# Adafruit_Feather_Zero_BLE_rev_B.net
KiCad netlist of a schematic drawn in EAGLE
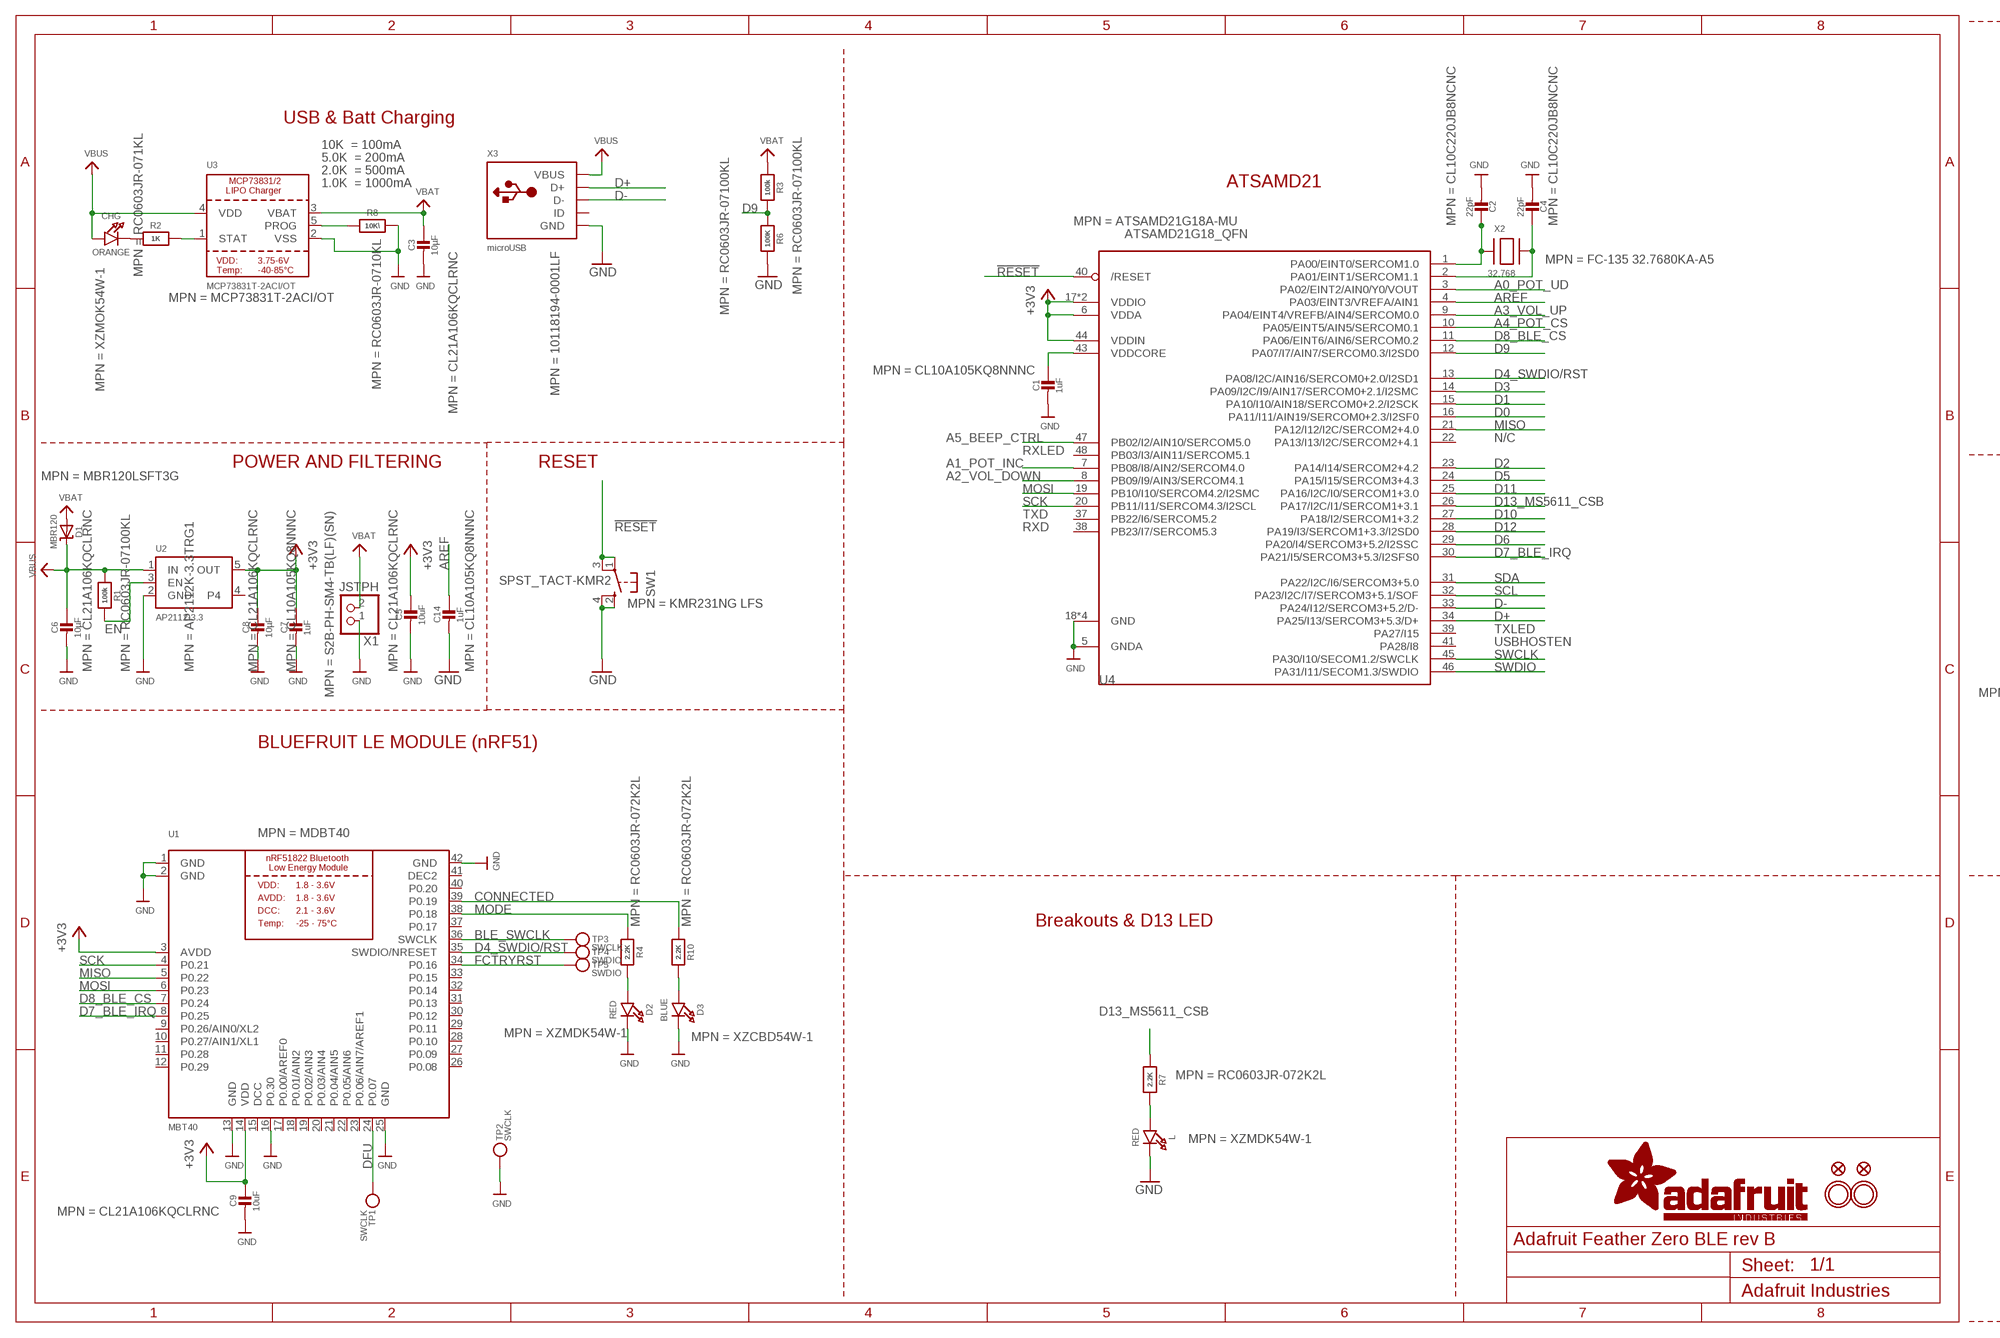
[diagram p0: schematic, sheet 1, part 1 of 2]
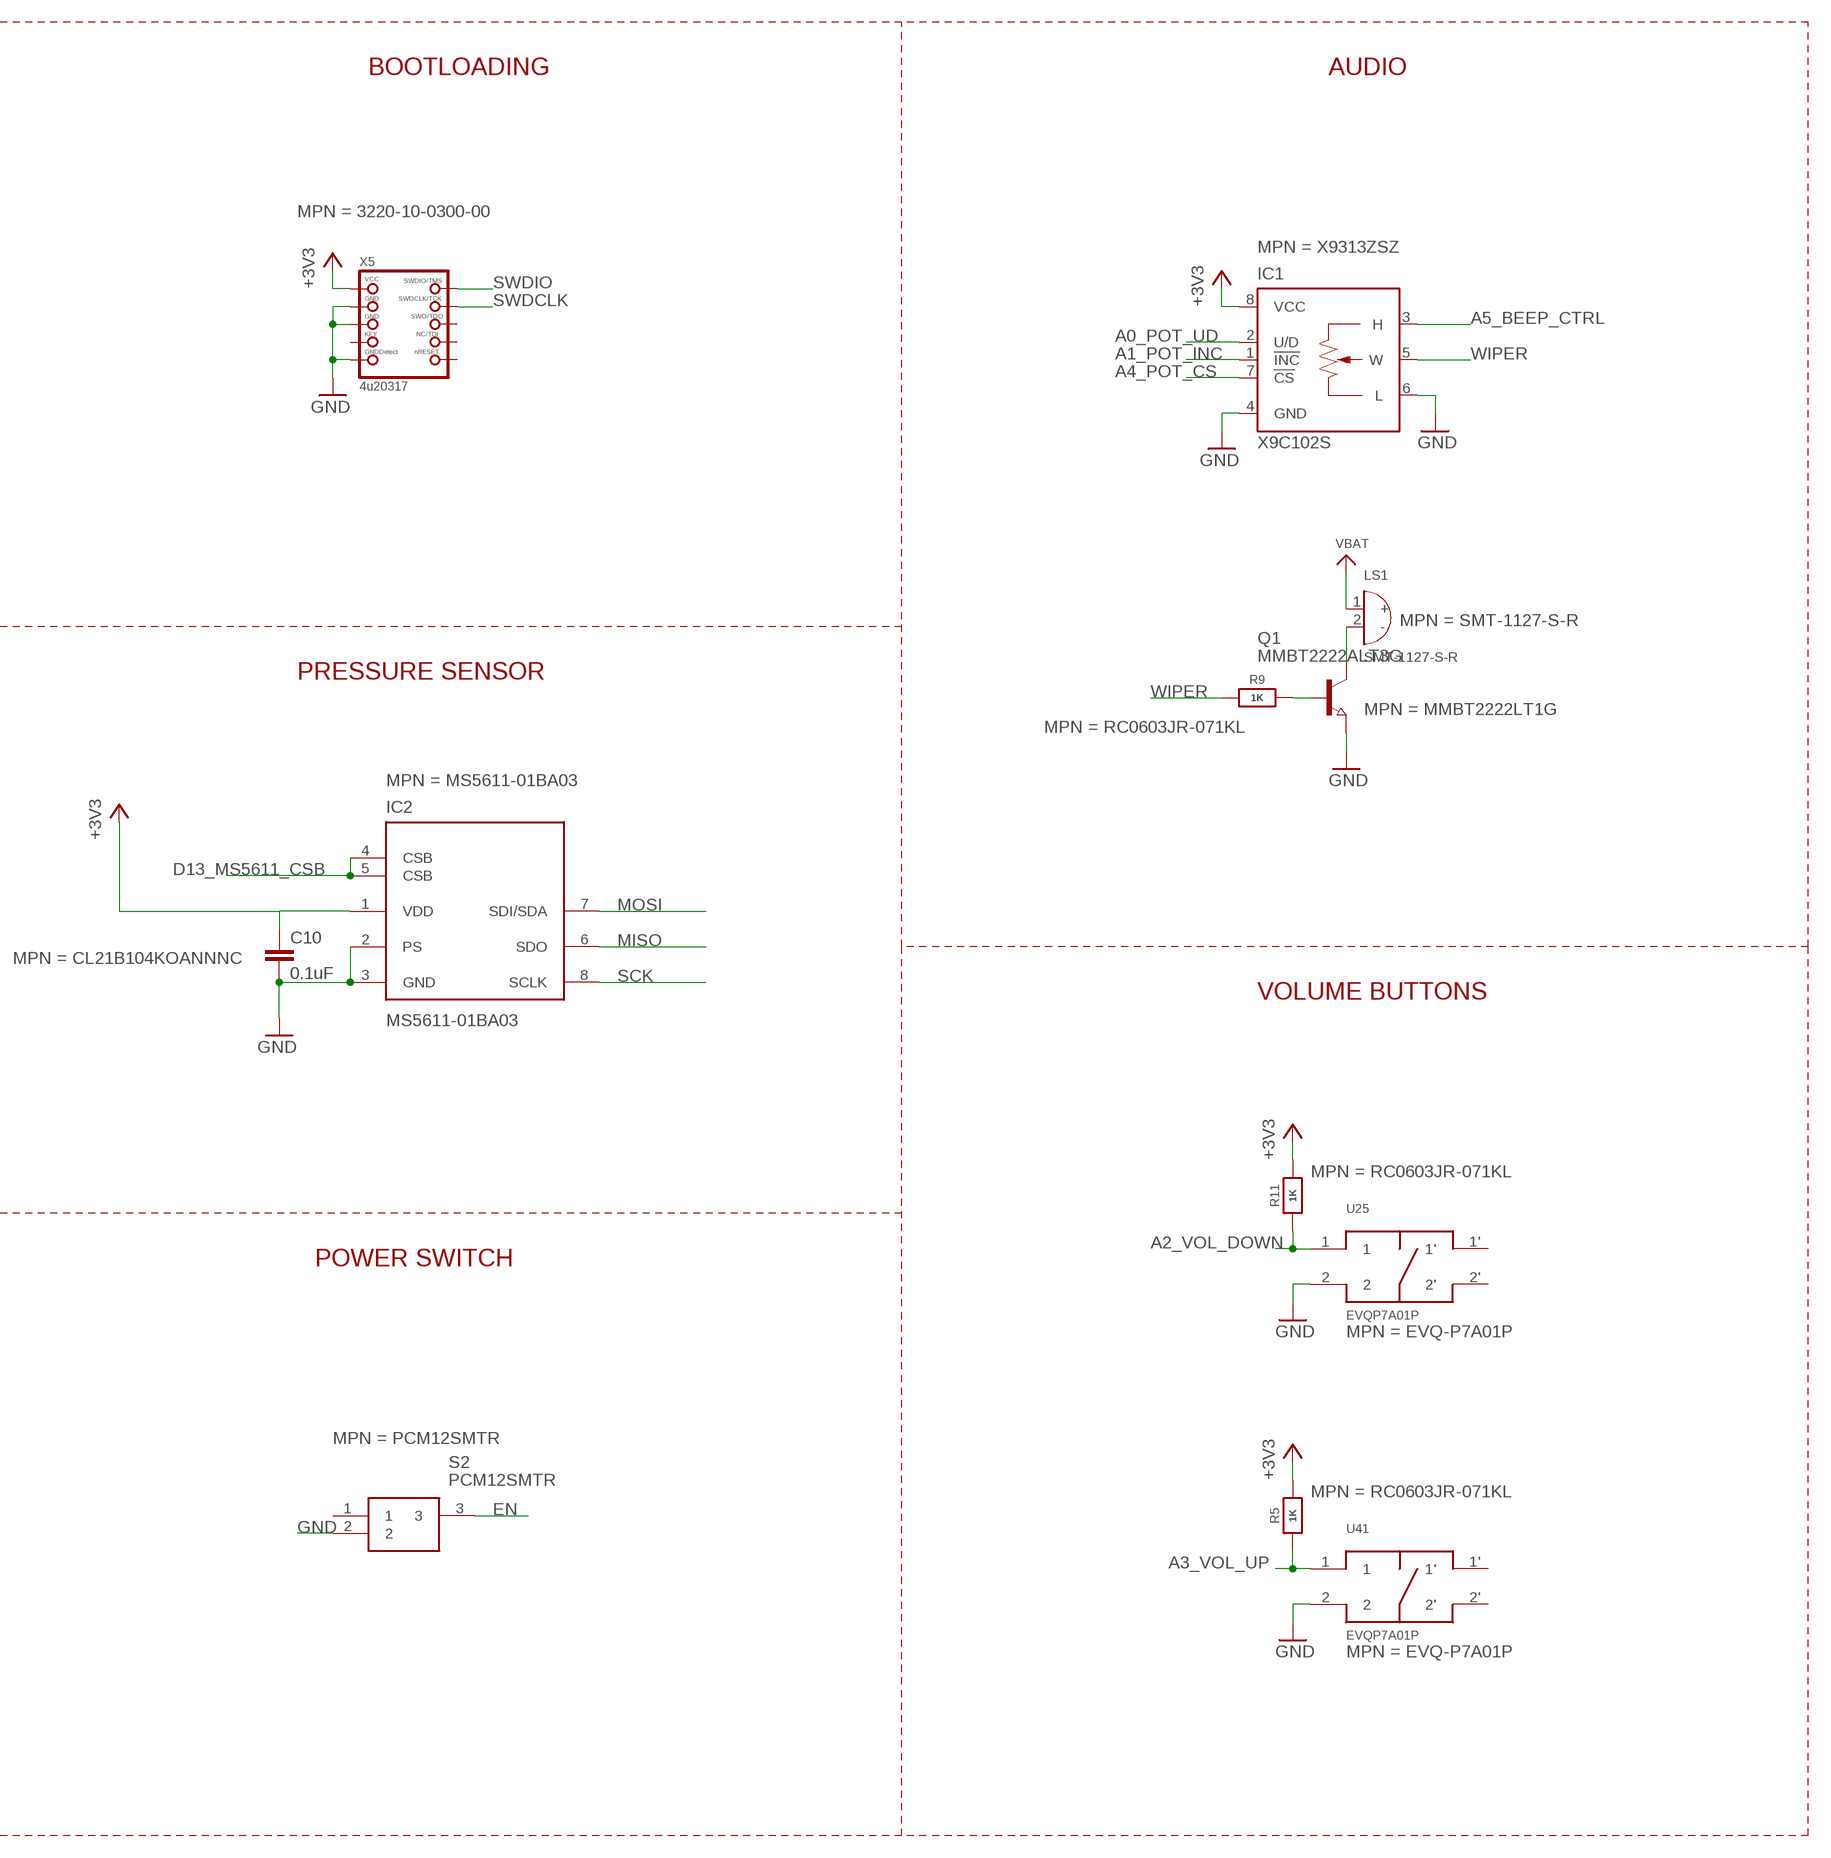
[diagram p1: schematic, sheet 1, part 2 of 2]

(export (version "E")
  (design (tool "Eeschema 10.0.6"))
  (components
    (comp (ref "C1")
      (value "1uF")
      (footprint "eagle-import:0603-NO")
      (fields (field (name "MPN") "CL10A105KQ8NNNC"))
      (libsource (lib "eagle-import") (part "CAP_CERAMIC0603_NO"))
    )
    (comp (ref "C2")
      (value "22pF")
      (footprint "eagle-import:0603-NO")
      (fields (field (name "MPN") "CL10C220JB8NCNC"))
      (libsource (lib "eagle-import") (part "CAP_CERAMIC0603_NO"))
    )
    (comp (ref "C3")
      (value "10µF")
      (footprint "eagle-import:0805-NO")
      (fields (field (name "MPN") "CL21A106KQCLRNC"))
      (libsource (lib "eagle-import") (part "CAP_CERAMIC0805-NOOUTLINE"))
    )
    (comp (ref "C4")
      (value "22pF")
      (footprint "eagle-import:0603-NO")
      (fields (field (name "MPN") "CL10C220JB8NCNC"))
      (libsource (lib "eagle-import") (part "CAP_CERAMIC0603_NO"))
    )
    (comp (ref "C5")
      (value "10uF")
      (footprint "eagle-import:0805-NO")
      (fields (field (name "MPN") "CL21A106KQCLRNC"))
      (libsource (lib "eagle-import") (part "CAP_CERAMIC0805-NOOUTLINE"))
    )
    (comp (ref "C6")
      (value "10µF")
      (footprint "eagle-import:0805-NO")
      (fields (field (name "MPN") "CL21A106KQCLRNC"))
      (libsource (lib "eagle-import") (part "CAP_CERAMIC0805-NOOUTLINE"))
    )
    (comp (ref "C7")
      (value "1uF")
      (footprint "eagle-import:0603-NO")
      (fields (field (name "MPN") "CL10A105KQ8NNNC"))
      (libsource (lib "eagle-import") (part "CAP_CERAMIC0603_NO"))
    )
    (comp (ref "C8")
      (value "10µF")
      (footprint "eagle-import:0805-NO")
      (fields (field (name "MPN") "CL21A106KQCLRNC"))
      (libsource (lib "eagle-import") (part "CAP_CERAMIC0805-NOOUTLINE"))
    )
    (comp (ref "C9")
      (value "10uF")
      (footprint "eagle-import:0805-NO")
      (fields (field (name "MPN") "CL21A106KQCLRNC"))
      (libsource (lib "eagle-import") (part "CAP_CERAMIC0805-NOOUTLINE"))
    )
    (comp (ref "C10")
      (value "0.1uF")
      (footprint "eagle-import:C0805K")
      (fields (field (name "MPN") "CL21B104KOANNNC"))
      (libsource (lib "eagle-import") (part "C-EUC0805K"))
    )
    (comp (ref "C14")
      (value "1uF")
      (footprint "eagle-import:0603-NO")
      (fields (field (name "MPN") "CL10A105KQ8NNNC"))
      (libsource (lib "eagle-import") (part "CAP_CERAMIC0603_NO"))
    )
    (comp (ref "CHG")
      (value "ORANGE")
      (footprint "eagle-import:CHIPLED_0805_NOOUTLINE")
      (fields (field (name "MPN") "XZMOK54W-1"))
      (libsource (lib "eagle-import") (part "LED0805_NOOUTLINE"))
    )
    (comp (ref "D1")
      (value "MBR120")
      (footprint "eagle-import:SOD-123")
      (fields (field (name "MPN") "MBR120LSFT3G"))
      (libsource (lib "eagle-import") (part "DIODE-SCHOTTKYSOD-123"))
    )
    (comp (ref "D2")
      (value "RED")
      (footprint "eagle-import:CHIPLED_0805_NOOUTLINE")
      (fields (field (name "MPN") "XZMDK54W-1"))
      (libsource (lib "eagle-import") (part "LED0805_NOOUTLINE"))
    )
    (comp (ref "D3")
      (value "BLUE")
      (footprint "eagle-import:CHIPLED_0805_NOOUTLINE")
      (fields (field (name "MPN") "XZCBD54W-1"))
      (libsource (lib "eagle-import") (part "LED0805_NOOUTLINE"))
    )
    (comp (ref "IC1")
      (value "X9C102S")
      (footprint "eagle-import:SOIC08")
      (fields
        (field (name "MF") "INTERSIL")
        (field (name "MPN") "X9C102SIZ")
        (field (name "MPN_1") "X9313ZSZ")
      )
      (libsource (lib "eagle-import") (part "X9C102S"))
    )
    (comp (ref "IC2")
      (value "MS5611-01BA03")
      (footprint "eagle-import:SON125P300X500X100-8N")
      (fields (field (name "MPN") "MS5611-01BA03"))
      (libsource (lib "eagle-import") (part "MS5611-01BA03UNO"))
    )
    (comp (ref "L")
      (value "RED")
      (footprint "eagle-import:CHIPLED_0805_NOOUTLINE")
      (fields (field (name "MPN") "XZMDK54W-1"))
      (libsource (lib "eagle-import") (part "LED0805_NOOUTLINE"))
    )
    (comp (ref "LS1")
      (value "SMT-1127-S-R")
      (footprint "eagle-import:XDCR_SMT-1127-S-R")
      (description "Black Passive Electromagnetic SMD Buzzer 3V 80mA 2700Hz 92dB 9x3.2mm")
      (fields
        (field (name "MF") "PUI Audio")
        (field (name "MP") "BOT-03D-BUJEON, SMT-1127-S-R")
        (field (name "MPN") "SMT-1127-S-R")
      )
      (libsource (lib "eagle-import") (part "SMT-1127-S-R"))
    )
    (comp (ref "Q1")
      (value "MMBT2222ALT3G")
      (footprint "eagle-import:SOT23")
      (fields (field (name "MPN") "MMBT2222LT1G"))
      (libsource (lib "eagle-import") (part "NPN-TRANSISTOR_SOT23"))
    )
    (comp (ref "R1")
      (value "100k")
      (footprint "eagle-import:0603-NO")
      (fields (field (name "MPN") "RC0603JR-07100KL"))
      (libsource (lib "eagle-import") (part "RESISTOR_0603_NOOUT"))
    )
    (comp (ref "R2")
      (value "1K")
      (footprint "eagle-import:0603-NO")
      (fields (field (name "MPN") "RC0603JR-071KL"))
      (libsource (lib "eagle-import") (part "RESISTOR_0603_NOOUT"))
    )
    (comp (ref "R3")
      (value "100k")
      (footprint "eagle-import:0603-NO")
      (fields (field (name "MPN") "RC0603JR-07100KL"))
      (libsource (lib "eagle-import") (part "RESISTOR_0603_NOOUT"))
    )
    (comp (ref "R4")
      (value "2.2K")
      (footprint "eagle-import:0603-NO")
      (fields (field (name "MPN") "RC0603JR-072K2L"))
      (libsource (lib "eagle-import") (part "RESISTOR_0603_NOOUT"))
    )
    (comp (ref "R5")
      (value "1K")
      (footprint "eagle-import:0603-NO")
      (fields (field (name "MPN") "RC0603JR-071KL"))
      (libsource (lib "eagle-import") (part "RESISTOR_0603_NOOUT"))
    )
    (comp (ref "R6")
      (value "100K")
      (footprint "eagle-import:0603-NO")
      (fields (field (name "MPN") "RC0603JR-07100KL"))
      (libsource (lib "eagle-import") (part "RESISTOR_0603_NOOUT"))
    )
    (comp (ref "R7")
      (value "2.2K")
      (footprint "eagle-import:0603-NO")
      (fields (field (name "MPN") "RC0603JR-072K2L"))
      (libsource (lib "eagle-import") (part "RESISTOR_0603_NOOUT"))
    )
    (comp (ref "R8")
      (value "10K\\")
      (footprint "eagle-import:0603-NO")
      (fields (field (name "MPN") "RC0603JR-0710KL"))
      (libsource (lib "eagle-import") (part "RESISTOR_0603_NOOUT"))
    )
    (comp (ref "R9")
      (value "1K")
      (footprint "eagle-import:0603-NO")
      (fields (field (name "MPN") "RC0603JR-071KL"))
      (libsource (lib "eagle-import") (part "RESISTOR_0603_NOOUT"))
    )
    (comp (ref "R10")
      (value "2.2K")
      (footprint "eagle-import:0603-NO")
      (fields (field (name "MPN") "RC0603JR-072K2L"))
      (libsource (lib "eagle-import") (part "RESISTOR_0603_NOOUT"))
    )
    (comp (ref "R11")
      (value "1K")
      (footprint "eagle-import:0603-NO")
      (fields (field (name "MPN") "RC0603JR-071KL"))
      (libsource (lib "eagle-import") (part "RESISTOR_0603_NOOUT"))
    )
    (comp (ref "S2")
      (value "PCM12SMTR")
      (footprint "eagle-import:PCM12SMTR_1")
      (fields (field (name "RS_PART_NUMBER") "7931721P") (field (name "MPN") "PCM12SMTR"))
      (libsource (lib "eagle-import") (part "PCM12SMTR"))
    )
    (comp (ref "SW1")
      (value "SPST_TACT-KMR2")
      (footprint "eagle-import:KMR2")
      (fields (field (name "MPN") "KMR231NG LFS"))
      (libsource (lib "eagle-import") (part "SPST_TACT-KMR2"))
    )
    (comp (ref "TP1")
      (value "SWCLK")
      (footprint "eagle-import:PAD-1.5X2.0")
      (libsource (lib "eagle-import") (part "TESTPOINT1.5X2.0MM_NOCREAM"))
    )
    (comp (ref "TP2")
      (value "SWCLK")
      (footprint "eagle-import:PAD-1.5X2.0")
      (libsource (lib "eagle-import") (part "TESTPOINT1.5X2.0MM_NOCREAM"))
    )
    (comp (ref "TP3")
      (value "SWCLK")
      (footprint "eagle-import:PAD-1.5X2.0")
      (libsource (lib "eagle-import") (part "TESTPOINT1.5X2.0MM_NOCREAM"))
    )
    (comp (ref "TP4")
      (value "SWDIO")
      (footprint "eagle-import:PAD-1.5X2.0")
      (libsource (lib "eagle-import") (part "TESTPOINT1.5X2.0MM_NOCREAM"))
    )
    (comp (ref "TP5")
      (value "SWDIO")
      (footprint "eagle-import:PAD-1.5X2.0")
      (libsource (lib "eagle-import") (part "TESTPOINT1.5X2.0MM_NOCREAM"))
    )
    (comp (ref "U$31")
      (value "MOUNTINGHOLE2.5")
      (footprint "eagle-import:MOUNTINGHOLE_2.5_PLATED")
      (libsource (lib "eagle-import") (part "MOUNTINGHOLE2.5"))
    )
    (comp (ref "U$32")
      (value "MOUNTINGHOLE2.5")
      (footprint "eagle-import:MOUNTINGHOLE_2.5_PLATED")
      (libsource (lib "eagle-import") (part "MOUNTINGHOLE2.5"))
    )
    (comp (ref "U$34")
      (value "FIDUCIAL\"\"")
      (footprint "eagle-import:FIDUCIAL_1MM")
      (libsource (lib "eagle-import") (part "FIDUCIAL{dblquote}{dblquote}"))
    )
    (comp (ref "U$35")
      (value "FIDUCIAL\"\"")
      (footprint "eagle-import:FIDUCIAL_1MM")
      (libsource (lib "eagle-import") (part "FIDUCIAL{dblquote}{dblquote}"))
    )
    (comp (ref "U1")
      (value "MBT40")
      (footprint "eagle-import:BLE_MODULE_RAYTAC_MDBT40")
      (fields (field (name "MPN") "MDBT40"))
      (libsource (lib "eagle-import") (part "NRF51822_MODULE_MDBT40"))
    )
    (comp (ref "U2")
      (value "AP2112-3.3")
      (footprint "eagle-import:SOT23-5")
      (fields (field (name "MPN") "AP2112K-3.3TRG1"))
      (libsource (lib "eagle-import") (part "VREG_SOT23-5"))
    )
    (comp (ref "U3")
      (value "MCP73831T-2ACI/OT")
      (footprint "eagle-import:SOT23-5")
      (fields (field (name "MPN") "MCP73831T-2ACI/OT"))
      (libsource (lib "eagle-import") (part "MCP73831/2"))
    )
    (comp (ref "U4")
      (value "ATSAMD21G18_QFN")
      (footprint "eagle-import:TQFN48_7MM")
      (fields (field (name "MPN") "ATSAMD21G18A-MU"))
      (libsource (lib "eagle-import") (part "ATSAMD21J_QFN"))
    )
    (comp (ref "U25")
      (value "EVQP7A01P")
      (footprint "eagle-import:EVQP7A01P")
      (fields (field (name "MPN") "EVQ-P7A01P"))
      (libsource (lib "eagle-import") (part "EVQP7A01P"))
    )
    (comp (ref "U41")
      (value "EVQP7A01P")
      (footprint "eagle-import:EVQP7A01P")
      (fields (field (name "MPN") "EVQ-P7A01P"))
      (libsource (lib "eagle-import") (part "EVQP7A01P"))
    )
    (comp (ref "X1")
      (value "JSTPH")
      (footprint "eagle-import:JSTPH2")
      (fields (field (name "MPN") "S2B-PH-SM4-TB(LF)(SN)"))
      (libsource (lib "eagle-import") (part "CON_JST_PH_2PIN"))
    )
    (comp (ref "X2")
      (value "32.768")
      (footprint "eagle-import:XTAL3215")
      (fields (field (name "MPN") "FC-135 32.7680KA-A5"))
      (libsource (lib "eagle-import") (part "XTAL-3.2X1.5"))
    )
    (comp (ref "X3")
      (value "microUSB")
      (footprint "eagle-import:4UCONN_20329_V2")
      (fields (field (name "MPN") "10118194-0001LF"))
      (libsource (lib "eagle-import") (part "USB_MICRO_20329_V2"))
    )
    (comp (ref "X5")
      (value "4u20317")
      (footprint "eagle-import:2X05_1.27MM_BOX_POSTS")
      (fields (field (name "MPN") "3220-10-0300-00"))
      (libsource (lib "eagle-import") (part "JTAG-CORTEXBOXPOSTS"))
    )
  )
  (nets
    (net (code "1") (name "+3V3") (class "Default")
      (node (ref "C10") (pin "1") (pinfunction "1_1") (pintype "passive"))
      (node (ref "C5") (pin "1") (pinfunction "1_1") (pintype "passive"))
      (node (ref "C7") (pin "1") (pinfunction "1_1") (pintype "passive"))
      (node (ref "C8") (pin "1") (pinfunction "1_1") (pintype "passive"))
      (node (ref "C9") (pin "1") (pinfunction "1_1") (pintype "passive"))
      (node (ref "IC1") (pin "8") (pinfunction "VCC_8") (pintype "power_in"))
      (node (ref "IC2") (pin "1") (pinfunction "VDD_1") (pintype "power_in"))
      (node (ref "R11") (pin "2") (pinfunction "2_2") (pintype "passive"))
      (node (ref "R5") (pin "2") (pinfunction "2_2") (pintype "passive"))
      (node (ref "U1") (pin "14") (pinfunction "VDD_14") (pintype "power_in"))
      (node (ref "U1") (pin "3") (pinfunction "AVDD_3") (pintype "power_in"))
      (node (ref "U2") (pin "5") (pinfunction "OUT_5") (pintype "power_in"))
      (node (ref "U4") (pin "17") (pinfunction "VDDIO_17") (pintype "power_in"))
      (node (ref "U4") (pin "36") (pinfunction "VDDIO_36") (pintype "power_in"))
      (node (ref "U4") (pin "44") (pinfunction "VDDIN_44") (pintype "power_in"))
      (node (ref "U4") (pin "6") (pinfunction "VDDA_6") (pintype "power_in"))
      (node (ref "X5") (pin "1") (pinfunction "VCC_1") (pintype "power_in"))
    )
    (net (code "2") (name "/A0_POT_UD") (class "Default")
      (node (ref "IC1") (pin "2") (pinfunction "U/D_2") (pintype "input"))
      (node (ref "U4") (pin "3") (pinfunction "PA02/EINT2/AIN0/Y0/VOUT_3") (pintype "bidirectional"))
    )
    (net (code "3") (name "/A1_POT_INC") (class "Default")
      (node (ref "IC1") (pin "1") (pinfunction "~{INC}_1") (pintype "input"))
      (node (ref "U4") (pin "7") (pinfunction "PB08/I8/AIN2/SERCOM4.0_7") (pintype "bidirectional"))
    )
    (net (code "4") (name "/A2_VOL_DOWN") (class "Default")
      (node (ref "R11") (pin "1") (pinfunction "1_1") (pintype "passive"))
      (node (ref "U25") (pin "1") (pinfunction "1_1") (pintype "bidirectional"))
      (node (ref "U4") (pin "8") (pinfunction "PB09/I9/AIN3/SERCOM4.1_8") (pintype "bidirectional"))
    )
    (net (code "5") (name "/A3_VOL_UP") (class "Default")
      (node (ref "R5") (pin "1") (pinfunction "1_1") (pintype "passive"))
      (node (ref "U4") (pin "9") (pinfunction "PA04/EINT4/VREFB/AIN4/SERCOM0.0_9") (pintype "bidirectional"))
      (node (ref "U41") (pin "1") (pinfunction "1_1") (pintype "bidirectional"))
    )
    (net (code "6") (name "/A4_POT_CS") (class "Default")
      (node (ref "IC1") (pin "7") (pinfunction "~{CS}_7") (pintype "input"))
      (node (ref "U4") (pin "10") (pinfunction "PA05/EINT5/AIN5/SERCOM0.1_10") (pintype "bidirectional"))
    )
    (net (code "7") (name "/A5_BEEP_CTRL") (class "Default")
      (node (ref "IC1") (pin "3") (pinfunction "H_3") (pintype "passive"))
      (node (ref "U4") (pin "47") (pinfunction "PB02/I2/AIN10/SERCOM5.0_47") (pintype "bidirectional"))
    )
    (net (code "8") (name "/AREF") (class "Default")
      (node (ref "C14") (pin "1") (pinfunction "1_1") (pintype "passive"))
      (node (ref "U4") (pin "4") (pinfunction "PA03/EINT3/VREFA/AIN1_4") (pintype "bidirectional"))
    )
    (net (code "9") (name "/BLE_SWCLK") (class "Default")
      (node (ref "TP3") (pin "P$1") (pinfunction "P$1_P$1") (pintype "bidirectional"))
      (node (ref "U1") (pin "36") (pinfunction "SWCLK_36") (pintype "bidirectional"))
    )
    (net (code "10") (name "/CONNECTED") (class "Default")
      (node (ref "R10") (pin "1") (pinfunction "1_1") (pintype "passive"))
      (node (ref "U1") (pin "39") (pinfunction "P0.19_39") (pintype "bidirectional"))
    )
    (net (code "11") (name "/D+") (class "Default")
      (node (ref "U4") (pin "34") (pinfunction "PA25/I13/SERCOM3+5.3/D+_34") (pintype "bidirectional"))
      (node (ref "X3") (pin "D+") (pinfunction "D+_D+") (pintype "bidirectional"))
    )
    (net (code "12") (name "/D-") (class "Default")
      (node (ref "U4") (pin "33") (pinfunction "PA24/I12/SERCOM3+5.2/D-_33") (pintype "bidirectional"))
      (node (ref "X3") (pin "D-") (pinfunction "D-_D-") (pintype "bidirectional"))
    )
    (net (code "13") (name "/D0") (class "Default")
      (node (ref "U4") (pin "16") (pinfunction "PA11/I11/AIN19/SERCOM0+2.3/I2SF0_16") (pintype "bidirectional"))
    )
    (net (code "14") (name "/D1") (class "Default")
      (node (ref "U4") (pin "15") (pinfunction "PA10/I10/AIN18/SERCOM0+2.2/I2SCK_15") (pintype "bidirectional"))
    )
    (net (code "15") (name "/D2") (class "Default")
      (node (ref "U4") (pin "23") (pinfunction "PA14/I14/SERCOM2+4.2_23") (pintype "bidirectional"))
    )
    (net (code "16") (name "/D3") (class "Default")
      (node (ref "U4") (pin "14") (pinfunction "PA09/I2C/I9/AIN17/SERCOM0+2.1/I2SMC_14") (pintype "bidirectional"))
    )
    (net (code "17") (name "/D4_SWDIO{slash}RST") (class "Default")
      (node (ref "TP4") (pin "P$1") (pinfunction "P$1_P$1") (pintype "bidirectional"))
      (node (ref "U1") (pin "35") (pinfunction "SWDIO/NRESET_35") (pintype "bidirectional"))
      (node (ref "U4") (pin "13") (pinfunction "PA08/I2C/AIN16/SERCOM0+2.0/I2SD1_13") (pintype "bidirectional"))
    )
    (net (code "18") (name "/D5") (class "Default")
      (node (ref "U4") (pin "24") (pinfunction "PA15/I15/SERCOM3+4.3_24") (pintype "bidirectional"))
    )
    (net (code "19") (name "/D6") (class "Default")
      (node (ref "U4") (pin "29") (pinfunction "PA20/I4/SERCOM3+5.2/I2SSC_29") (pintype "bidirectional"))
    )
    (net (code "20") (name "/D7_BLE_IRQ") (class "Default")
      (node (ref "U1") (pin "8") (pinfunction "P0.25_8") (pintype "bidirectional"))
      (node (ref "U4") (pin "30") (pinfunction "PA21/I5/SERCOM3+5.3/I2SFS0_30") (pintype "bidirectional"))
    )
    (net (code "21") (name "/D8_BLE_CS") (class "Default")
      (node (ref "U1") (pin "7") (pinfunction "P0.24_7") (pintype "bidirectional"))
      (node (ref "U4") (pin "11") (pinfunction "PA06/EINT6/AIN6/SERCOM0.2_11") (pintype "bidirectional"))
    )
    (net (code "22") (name "/D9") (class "Default")
      (node (ref "R3") (pin "2") (pinfunction "2_2") (pintype "passive"))
      (node (ref "R6") (pin "1") (pinfunction "1_1") (pintype "passive"))
      (node (ref "U4") (pin "12") (pinfunction "PA07/I7/AIN7/SERCOM0.3/I2SD0_12") (pintype "bidirectional"))
    )
    (net (code "23") (name "/D10") (class "Default")
      (node (ref "U4") (pin "27") (pinfunction "PA18/I2/SERCOM1+3.2_27") (pintype "bidirectional"))
    )
    (net (code "24") (name "/D11") (class "Default")
      (node (ref "U4") (pin "25") (pinfunction "PA16/I2C/I0/SERCOM1+3.0_25") (pintype "bidirectional"))
    )
    (net (code "25") (name "/D12") (class "Default")
      (node (ref "U4") (pin "28") (pinfunction "PA19/I3/SERCOM1+3.3/I2SD0_28") (pintype "bidirectional"))
    )
    (net (code "26") (name "/D13_MS5611_CSB") (class "Default")
      (node (ref "IC2") (pin "4") (pinfunction "CSB_4") (pintype "input"))
      (node (ref "IC2") (pin "5") (pinfunction "CSB_5") (pintype "input"))
      (node (ref "R7") (pin "1") (pinfunction "1_1") (pintype "passive"))
      (node (ref "U4") (pin "26") (pinfunction "PA17/I2C/I1/SERCOM1+3.1_26") (pintype "bidirectional"))
    )
    (net (code "27") (name "/DCC") (class "Default")
      (node (ref "U1") (pin "15") (pinfunction "DCC_15") (pintype "power_in"))
    )
    (net (code "28") (name "/DEC2") (class "Default")
      (node (ref "U1") (pin "41") (pinfunction "DEC2_41") (pintype "power_in"))
    )
    (net (code "29") (name "/DFU") (class "Default")
      (node (ref "TP1") (pin "P$1") (pinfunction "P$1_P$1") (pintype "bidirectional"))
      (node (ref "U1") (pin "24") (pinfunction "P0.07_24") (pintype "bidirectional"))
    )
    (net (code "30") (name "/EN") (class "Default")
      (node (ref "R1") (pin "2") (pinfunction "2_2") (pintype "passive"))
      (node (ref "S2") (pin "3") (pinfunction "3_3") (pintype "input"))
      (node (ref "U2") (pin "3") (pinfunction "EN_3") (pintype "input"))
    )
    (net (code "31") (name "/FCTRYRST") (class "Default")
      (node (ref "TP5") (pin "P$1") (pinfunction "P$1_P$1") (pintype "bidirectional"))
      (node (ref "U1") (pin "34") (pinfunction "P0.16_34") (pintype "bidirectional"))
    )
    (net (code "32") (name "/MISO") (class "Default")
      (node (ref "IC2") (pin "6") (pinfunction "SDO_6") (pintype "output"))
      (node (ref "U1") (pin "5") (pinfunction "P0.22_5") (pintype "bidirectional"))
      (node (ref "U4") (pin "21") (pinfunction "PA12/I12/I2C/SERCOM2+4.0_21") (pintype "bidirectional"))
    )
    (net (code "33") (name "/MODE") (class "Default")
      (node (ref "R4") (pin "1") (pinfunction "1_1") (pintype "passive"))
      (node (ref "U1") (pin "38") (pinfunction "P0.18_38") (pintype "bidirectional"))
    )
    (net (code "34") (name "/MOSI") (class "Default")
      (node (ref "IC2") (pin "7") (pinfunction "SDI/SDA_7") (pintype "bidirectional"))
      (node (ref "U1") (pin "6") (pinfunction "P0.23_6") (pintype "bidirectional"))
      (node (ref "U4") (pin "19") (pinfunction "PB10/I10/SERCOM4.2/I2SMC_19") (pintype "bidirectional"))
    )
    (net (code "35") (name "/SCK") (class "Default")
      (node (ref "IC2") (pin "8") (pinfunction "SCLK_8") (pintype "input"))
      (node (ref "U1") (pin "4") (pinfunction "P0.21_4") (pintype "bidirectional"))
      (node (ref "U4") (pin "20") (pinfunction "PB11/I11/SERCOM4.3/I2SCL_20") (pintype "bidirectional"))
    )
    (net (code "36") (name "/SCL") (class "Default")
      (node (ref "U4") (pin "32") (pinfunction "PA23/I2C/I7/SERCOM3+5.1/SOF_32") (pintype "bidirectional"))
    )
    (net (code "37") (name "/SDA") (class "Default")
      (node (ref "U4") (pin "31") (pinfunction "PA22/I2C/I6/SERCOM3+5.0_31") (pintype "bidirectional"))
    )
    (net (code "38") (name "/SWCLK") (class "Default")
      (node (ref "U4") (pin "45") (pinfunction "PA30/I10/SECOM1.2/SWCLK_45") (pintype "bidirectional"))
    )
    (net (code "39") (name "/SWDCLK") (class "Default")
      (node (ref "X5") (pin "4") (pinfunction "SWDCLK_4") (pintype "bidirectional"))
    )
    (net (code "40") (name "/SWDIO") (class "Default")
      (node (ref "U4") (pin "46") (pinfunction "PA31/I11/SECOM1.3/SWDIO_46") (pintype "bidirectional"))
      (node (ref "X5") (pin "2") (pinfunction "SWDIO_2") (pintype "bidirectional"))
    )
    (net (code "41") (name "/WIPER") (class "Default")
      (node (ref "IC1") (pin "5") (pinfunction "W_5") (pintype "passive"))
      (node (ref "R9") (pin "1") (pinfunction "1_1") (pintype "passive"))
    )
    (net (code "42") (name "/~{RESET}") (class "Default")
      (node (ref "SW1") (pin "1") (pinfunction "P_1") (pintype "passive"))
      (node (ref "SW1") (pin "3") (pinfunction "P1_3") (pintype "passive"))
      (node (ref "U4") (pin "40") (pinfunction "/RESET_40") (pintype "bidirectional"))
    )
    (net (code "43") (name "GND") (class "Default")
      (node (ref "C1") (pin "2") (pinfunction "2_2") (pintype "passive"))
      (node (ref "C10") (pin "2") (pinfunction "2_2") (pintype "passive"))
      (node (ref "C14") (pin "2") (pinfunction "2_2") (pintype "passive"))
      (node (ref "C2") (pin "2") (pinfunction "2_2") (pintype "passive"))
      (node (ref "C3") (pin "2") (pinfunction "2_2") (pintype "passive"))
      (node (ref "C4") (pin "2") (pinfunction "2_2") (pintype "passive"))
      (node (ref "C5") (pin "2") (pinfunction "2_2") (pintype "passive"))
      (node (ref "C6") (pin "2") (pinfunction "2_2") (pintype "passive"))
      (node (ref "C7") (pin "2") (pinfunction "2_2") (pintype "passive"))
      (node (ref "C8") (pin "2") (pinfunction "2_2") (pintype "passive"))
      (node (ref "C9") (pin "2") (pinfunction "2_2") (pintype "passive"))
      (node (ref "D2") (pin "C") (pinfunction "C_C") (pintype "passive"))
      (node (ref "D3") (pin "C") (pinfunction "C_C") (pintype "passive"))
      (node (ref "IC1") (pin "4") (pinfunction "GND_4") (pintype "power_in"))
      (node (ref "IC1") (pin "6") (pinfunction "L_6") (pintype "passive"))
      (node (ref "IC2") (pin "2") (pinfunction "PS_2") (pintype "input"))
      (node (ref "IC2") (pin "3") (pinfunction "GND_3") (pintype "power_in"))
      (node (ref "L") (pin "C") (pinfunction "C_C") (pintype "passive"))
      (node (ref "Q1") (pin "2") (pinfunction "E_2") (pintype "passive"))
      (node (ref "R6") (pin "2") (pinfunction "2_2") (pintype "passive"))
      (node (ref "R8") (pin "2") (pinfunction "2_2") (pintype "passive"))
      (node (ref "S2") (pin "2") (pinfunction "2_2") (pintype "input"))
      (node (ref "SW1") (pin "2") (pinfunction "S_2") (pintype "passive"))
      (node (ref "SW1") (pin "4") (pinfunction "S1_4") (pintype "passive"))
      (node (ref "TP2") (pin "P$1") (pinfunction "P$1_P$1") (pintype "bidirectional"))
      (node (ref "U1") (pin "1") (pinfunction "GND_1") (pintype "power_in"))
      (node (ref "U1") (pin "13") (pinfunction "GND_13") (pintype "power_in"))
      (node (ref "U1") (pin "16") (pinfunction "P0.30_16") (pintype "bidirectional"))
      (node (ref "U1") (pin "2") (pinfunction "GND_2") (pintype "power_in"))
      (node (ref "U1") (pin "25") (pinfunction "GND_25") (pintype "power_in"))
      (node (ref "U1") (pin "42") (pinfunction "GND_42") (pintype "power_in"))
      (node (ref "U2") (pin "2") (pinfunction "GND_2") (pintype "power_in"))
      (node (ref "U25") (pin "2") (pinfunction "2_2") (pintype "bidirectional"))
      (node (ref "U3") (pin "2") (pinfunction "VSS_2") (pintype "power_in"))
      (node (ref "U4") (pin "18") (pinfunction "GND_18") (pintype "power_in"))
      (node (ref "U4") (pin "35") (pinfunction "GND_35") (pintype "power_in"))
      (node (ref "U4") (pin "42") (pinfunction "GND_42") (pintype "power_in"))
      (node (ref "U4") (pin "5") (pinfunction "GNDA_5") (pintype "power_in"))
      (node (ref "U4") (pin "THERMAL") (pinfunction "GND_THERMAL") (pintype "power_in"))
      (node (ref "U41") (pin "2") (pinfunction "2_2") (pintype "bidirectional"))
      (node (ref "X1") (pin "1") (pinfunction "1_1") (pintype "passive"))
      (node (ref "X3") (pin "BASE@1") (pinfunction "GND_BASE@1") (pintype "power_in"))
      (node (ref "X3") (pin "BASE@2") (pinfunction "GND_BASE@2") (pintype "power_in"))
      (node (ref "X3") (pin "GND") (pinfunction "GND_GND") (pintype "power_in"))
      (node (ref "X3") (pin "SPRT@1") (pinfunction "GND_SPRT@1") (pintype "power_in"))
      (node (ref "X3") (pin "SPRT@2") (pinfunction "GND_SPRT@2") (pintype "power_in"))
      (node (ref "X3") (pin "SPRT@3") (pinfunction "GND_SPRT@3") (pintype "power_in"))
      (node (ref "X3") (pin "SPRT@4") (pinfunction "GND_SPRT@4") (pintype "power_in"))
      (node (ref "X5") (pin "3") (pinfunction "GND_3") (pintype "power_in"))
      (node (ref "X5") (pin "5") (pinfunction "GND_5") (pintype "power_in"))
      (node (ref "X5") (pin "9") (pinfunction "GNDDETECT_9") (pintype "bidirectional"))
    )
    (net (code "44") (name "Net-(CHG-PadC)") (class "Default")
      (node (ref "CHG") (pin "C") (pinfunction "C_C") (pintype "passive"))
      (node (ref "R2") (pin "1") (pinfunction "1_1") (pintype "passive"))
    )
    (net (code "45") (name "Net-(D2-PadA)") (class "Default")
      (node (ref "D2") (pin "A") (pinfunction "A_A") (pintype "passive"))
      (node (ref "R4") (pin "2") (pinfunction "2_2") (pintype "passive"))
    )
    (net (code "46") (name "Net-(D3-PadA)") (class "Default")
      (node (ref "D3") (pin "A") (pinfunction "A_A") (pintype "passive"))
      (node (ref "R10") (pin "2") (pinfunction "2_2") (pintype "passive"))
    )
    (net (code "47") (name "Net-(L-PadA)") (class "Default")
      (node (ref "L") (pin "A") (pinfunction "A_A") (pintype "passive"))
      (node (ref "R7") (pin "2") (pinfunction "2_2") (pintype "passive"))
    )
    (net (code "48") (name "Net-(LS1--)") (class "Default")
      (node (ref "LS1") (pin "2") (pinfunction "-_2") (pintype "passive"))
      (node (ref "Q1") (pin "3") (pinfunction "C_3") (pintype "passive"))
    )
    (net (code "49") (name "Net-(Q1-B)") (class "Default")
      (node (ref "Q1") (pin "1") (pinfunction "B_1") (pintype "passive"))
      (node (ref "R9") (pin "2") (pinfunction "2_2") (pintype "passive"))
    )
    (net (code "50") (name "Net-(U3-PROG)") (class "Default")
      (node (ref "R8") (pin "1") (pinfunction "1_1") (pintype "passive"))
      (node (ref "U3") (pin "5") (pinfunction "PROG_5") (pintype "input"))
    )
    (net (code "51") (name "Net-(U3-STAT)") (class "Default")
      (node (ref "R2") (pin "2") (pinfunction "2_2") (pintype "passive"))
      (node (ref "U3") (pin "1") (pinfunction "STAT_1") (pintype "output"))
    )
    (net (code "52") (name "Net-(U4-PA00{slash}EINT0{slash}SERCOM1.0)") (class "Default")
      (node (ref "C2") (pin "1") (pinfunction "1_1") (pintype "passive"))
      (node (ref "U4") (pin "1") (pinfunction "PA00/EINT0/SERCOM1.0_1") (pintype "bidirectional"))
      (node (ref "X2") (pin "P$1") (pinfunction "P$1_P$1") (pintype "bidirectional"))
    )
    (net (code "53") (name "Net-(U4-PA01{slash}EINT1{slash}SERCOM1.1)") (class "Default")
      (node (ref "C4") (pin "1") (pinfunction "1_1") (pintype "passive"))
      (node (ref "U4") (pin "2") (pinfunction "PA01/EINT1/SERCOM1.1_2") (pintype "bidirectional"))
      (node (ref "X2") (pin "P$2") (pinfunction "P$2_P$2") (pintype "bidirectional"))
    )
    (net (code "54") (name "Net-(U4-VDDCORE)") (class "Default")
      (node (ref "C1") (pin "1") (pinfunction "1_1") (pintype "passive"))
      (node (ref "U4") (pin "43") (pinfunction "VDDCORE_43") (pintype "power_in"))
    )
    (net (code "55") (name "VBAT") (class "Default")
      (node (ref "C3") (pin "1") (pinfunction "1_1") (pintype "passive"))
      (node (ref "D1") (pin "A") (pinfunction "A_A") (pintype "passive"))
      (node (ref "LS1") (pin "1") (pinfunction "+_1") (pintype "passive"))
      (node (ref "R3") (pin "1") (pinfunction "1_1") (pintype "passive"))
      (node (ref "U3") (pin "3") (pinfunction "VBAT_3") (pintype "power_in"))
      (node (ref "X1") (pin "2") (pinfunction "2_2") (pintype "passive"))
    )
    (net (code "56") (name "VBUS") (class "Default")
      (node (ref "C6") (pin "1") (pinfunction "1_1") (pintype "passive"))
      (node (ref "CHG") (pin "A") (pinfunction "A_A") (pintype "passive"))
      (node (ref "D1") (pin "C") (pinfunction "C_C") (pintype "passive"))
      (node (ref "R1") (pin "1") (pinfunction "1_1") (pintype "passive"))
      (node (ref "U2") (pin "1") (pinfunction "IN_1") (pintype "power_in"))
      (node (ref "U3") (pin "4") (pinfunction "VDD_4") (pintype "power_in"))
      (node (ref "X3") (pin "VBUS") (pinfunction "VBUS_VBUS") (pintype "power_in"))
    )
    (net (code "57") (name "unconnected-(S2-Pad1)") (class "Default")
      (node (ref "S2") (pin "1") (pinfunction "1_1") (pintype "input"))
    )
    (net (code "58") (name "unconnected-(U1-P0.00{slash}AREF0-Pad17)") (class "Default")
      (node (ref "U1") (pin "17") (pinfunction "P0.00/AREF0_17") (pintype "bidirectional"))
    )
    (net (code "59") (name "unconnected-(U1-P0.01{slash}AIN2-Pad18)") (class "Default")
      (node (ref "U1") (pin "18") (pinfunction "P0.01/AIN2_18") (pintype "bidirectional"))
    )
    (net (code "60") (name "unconnected-(U1-P0.02{slash}AIN3-Pad19)") (class "Default")
      (node (ref "U1") (pin "19") (pinfunction "P0.02/AIN3_19") (pintype "bidirectional"))
    )
    (net (code "61") (name "unconnected-(U1-P0.03{slash}AIN4-Pad20)") (class "Default")
      (node (ref "U1") (pin "20") (pinfunction "P0.03/AIN4_20") (pintype "bidirectional"))
    )
    (net (code "62") (name "unconnected-(U1-P0.04{slash}AIN5-Pad21)") (class "Default")
      (node (ref "U1") (pin "21") (pinfunction "P0.04/AIN5_21") (pintype "bidirectional"))
    )
    (net (code "63") (name "unconnected-(U1-P0.05{slash}AIN6-Pad22)") (class "Default")
      (node (ref "U1") (pin "22") (pinfunction "P0.05/AIN6_22") (pintype "bidirectional"))
    )
    (net (code "64") (name "unconnected-(U1-P0.06{slash}AIN7{slash}AREF1-Pad23)") (class "Default")
      (node (ref "U1") (pin "23") (pinfunction "P0.06/AIN7/AREF1_23") (pintype "bidirectional"))
    )
    (net (code "65") (name "unconnected-(U1-P0.08-Pad26)") (class "Default")
      (node (ref "U1") (pin "26") (pinfunction "P0.08_26") (pintype "bidirectional"))
    )
    (net (code "66") (name "unconnected-(U1-P0.09-Pad27)") (class "Default")
      (node (ref "U1") (pin "27") (pinfunction "P0.09_27") (pintype "bidirectional"))
    )
    (net (code "67") (name "unconnected-(U1-P0.10-Pad28)") (class "Default")
      (node (ref "U1") (pin "28") (pinfunction "P0.10_28") (pintype "bidirectional"))
    )
    (net (code "68") (name "unconnected-(U1-P0.11-Pad29)") (class "Default")
      (node (ref "U1") (pin "29") (pinfunction "P0.11_29") (pintype "bidirectional"))
    )
    (net (code "69") (name "unconnected-(U1-P0.12-Pad30)") (class "Default")
      (node (ref "U1") (pin "30") (pinfunction "P0.12_30") (pintype "bidirectional"))
    )
    (net (code "70") (name "unconnected-(U1-P0.13-Pad31)") (class "Default")
      (node (ref "U1") (pin "31") (pinfunction "P0.13_31") (pintype "bidirectional"))
    )
    (net (code "71") (name "unconnected-(U1-P0.14-Pad32)") (class "Default")
      (node (ref "U1") (pin "32") (pinfunction "P0.14_32") (pintype "bidirectional"))
    )
    (net (code "72") (name "unconnected-(U1-P0.15-Pad33)") (class "Default")
      (node (ref "U1") (pin "33") (pinfunction "P0.15_33") (pintype "bidirectional"))
    )
    (net (code "73") (name "unconnected-(U1-P0.17-Pad37)") (class "Default")
      (node (ref "U1") (pin "37") (pinfunction "P0.17_37") (pintype "bidirectional"))
    )
    (net (code "74") (name "unconnected-(U1-P0.20-Pad40)") (class "Default")
      (node (ref "U1") (pin "40") (pinfunction "P0.20_40") (pintype "bidirectional"))
    )
    (net (code "75") (name "unconnected-(U1-P0.26{slash}AIN0{slash}XL2-Pad9)") (class "Default")
      (node (ref "U1") (pin "9") (pinfunction "P0.26/AIN0/XL2_9") (pintype "bidirectional"))
    )
    (net (code "76") (name "unconnected-(U1-P0.27{slash}AIN1{slash}XL1-Pad10)") (class "Default")
      (node (ref "U1") (pin "10") (pinfunction "P0.27/AIN1/XL1_10") (pintype "bidirectional"))
    )
    (net (code "77") (name "unconnected-(U1-P0.28-Pad11)") (class "Default")
      (node (ref "U1") (pin "11") (pinfunction "P0.28_11") (pintype "bidirectional"))
    )
    (net (code "78") (name "unconnected-(U1-P0.29-Pad12)") (class "Default")
      (node (ref "U1") (pin "12") (pinfunction "P0.29_12") (pintype "bidirectional"))
    )
    (net (code "79") (name "unconnected-(U2-P4-Pad4)") (class "Default")
      (node (ref "U2") (pin "4") (pinfunction "P4_4") (pintype "bidirectional"))
    )
    (net (code "80") (name "unconnected-(U4-PA13{slash}I13{slash}I2C{slash}SERCOM2+4.1-Pad22)") (class "Default")
      (node (ref "U4") (pin "22") (pinfunction "PA13/I13/I2C/SERCOM2+4.1_22") (pintype "bidirectional"))
    )
    (net (code "81") (name "unconnected-(U4-PA27{slash}I15-Pad39)") (class "Default")
      (node (ref "U4") (pin "39") (pinfunction "PA27/I15_39") (pintype "bidirectional"))
    )
    (net (code "82") (name "unconnected-(U4-PA28{slash}I8-Pad41)") (class "Default")
      (node (ref "U4") (pin "41") (pinfunction "PA28/I8_41") (pintype "bidirectional"))
    )
    (net (code "83") (name "unconnected-(U4-PB03{slash}I3{slash}AIN11{slash}SERCOM5.1-Pad48)") (class "Default")
      (node (ref "U4") (pin "48") (pinfunction "PB03/I3/AIN11/SERCOM5.1_48") (pintype "bidirectional"))
    )
    (net (code "84") (name "unconnected-(U4-PB22{slash}I6{slash}SERCOM5.2-Pad37)") (class "Default")
      (node (ref "U4") (pin "37") (pinfunction "PB22/I6/SERCOM5.2_37") (pintype "bidirectional"))
    )
    (net (code "85") (name "unconnected-(U4-PB23{slash}I7{slash}SERCOM5.3-Pad38)") (class "Default")
      (node (ref "U4") (pin "38") (pinfunction "PB23/I7/SERCOM5.3_38") (pintype "bidirectional"))
    )
    (net (code "86") (name "unconnected-(U25-Pad1')") (class "Default")
      (node (ref "U25") (pin "1'") (pinfunction "1'_1'") (pintype "bidirectional"))
    )
    (net (code "87") (name "unconnected-(U25-Pad2')") (class "Default")
      (node (ref "U25") (pin "2'") (pinfunction "2'_2'") (pintype "bidirectional"))
    )
    (net (code "88") (name "unconnected-(U41-Pad1')") (class "Default")
      (node (ref "U41") (pin "1'") (pinfunction "1'_1'") (pintype "bidirectional"))
    )
    (net (code "89") (name "unconnected-(U41-Pad2')") (class "Default")
      (node (ref "U41") (pin "2'") (pinfunction "2'_2'") (pintype "bidirectional"))
    )
    (net (code "90") (name "unconnected-(X3-PadID)") (class "Default")
      (node (ref "X3") (pin "ID") (pinfunction "ID_ID") (pintype "bidirectional"))
    )
    (net (code "91") (name "unconnected-(X5-KEY-Pad7)") (class "Default")
      (node (ref "X5") (pin "7") (pinfunction "KEY_7") (pintype "bidirectional"))
    )
    (net (code "92") (name "unconnected-(X5-NRESET-Pad10)") (class "Default")
      (node (ref "X5") (pin "10") (pinfunction "NRESET_10") (pintype "bidirectional"))
    )
    (net (code "93") (name "unconnected-(X5-SWO-Pad6)") (class "Default")
      (node (ref "X5") (pin "6") (pinfunction "SWO_6") (pintype "bidirectional"))
    )
    (net (code "94") (name "unconnected-(X5-TDI-Pad8)") (class "Default")
      (node (ref "X5") (pin "8") (pinfunction "TDI_8") (pintype "bidirectional"))
    )
  )
)
